# 6_Charger.net
KiCad netlist of a schematic drawn in Altium Designer
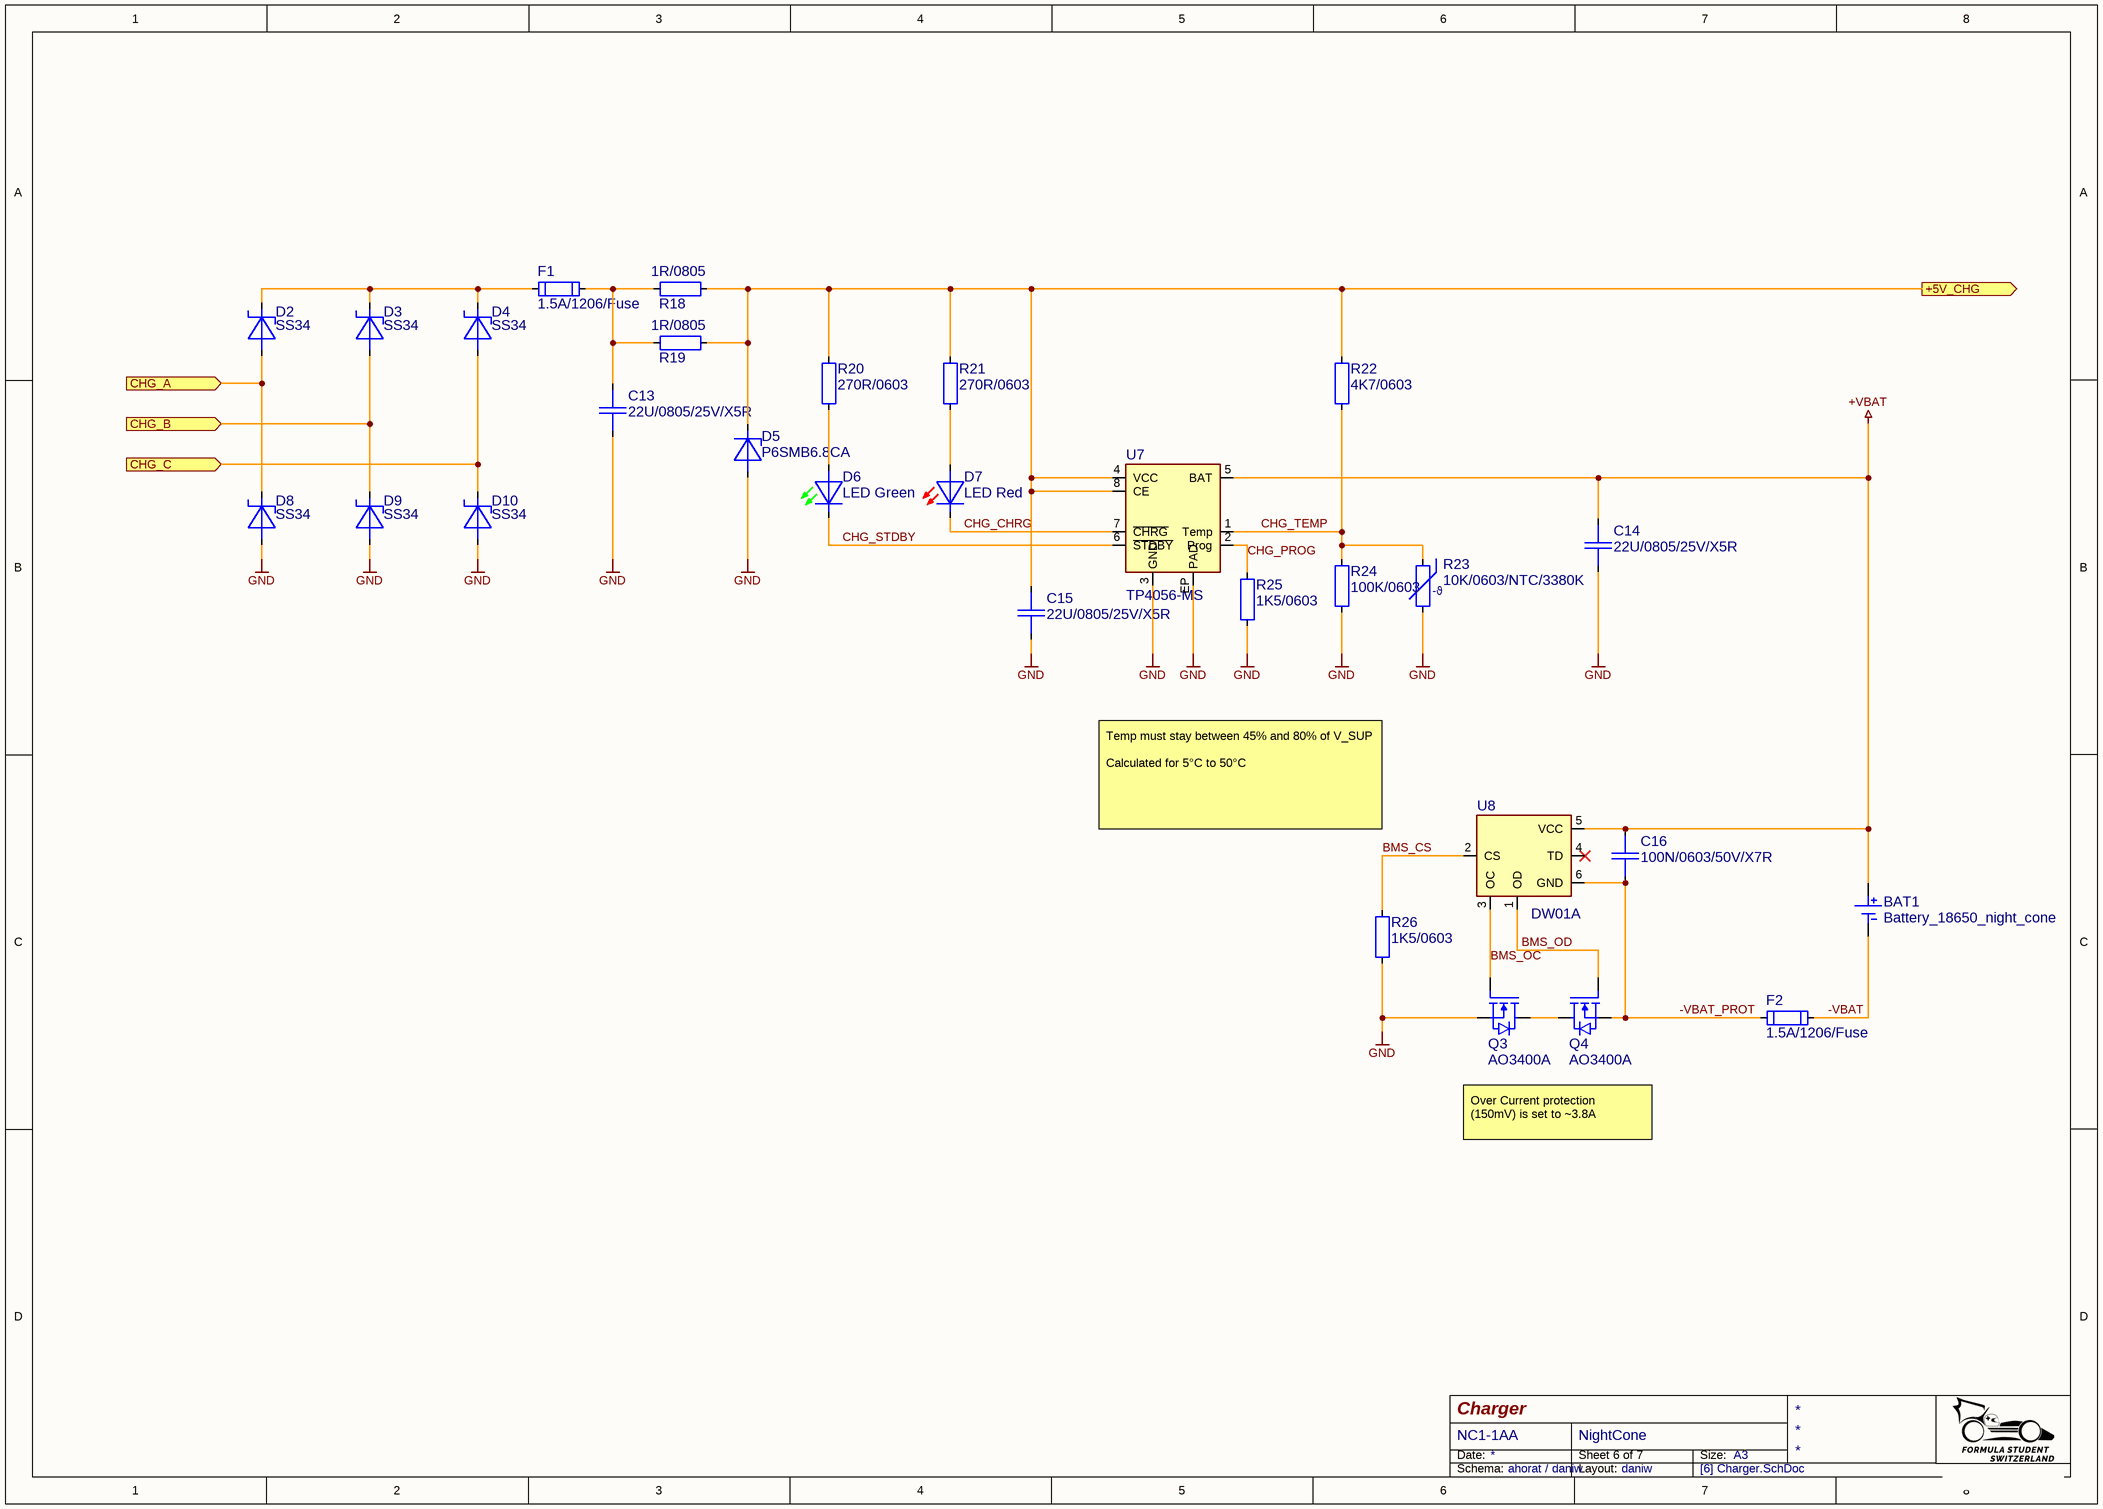
[diagram p0: [6] Charger.SchDoc]

(export (version "E")
  (design (tool "Eeschema 10.0.6"))
  (components
    (comp (ref "BAT1")
      (value "Battery_18650_night_cone")
      (footprint "Battery_18650_night_cone")
      (description "18650 Footprint with Hole for 18650 Battery")
      (fields (field (name "MANUFACTURER") "NONE"))
      (libsource (lib "daniw_altium_lib") (part "Battery_1"))
    )
    (comp (ref "C13")
      (value "22U/0805/25V/X5R")
      (footprint "CAP0805_X7R")
      (description "CAP SM 0805 22uF 25V X5R")
      (fields (field (name "MANUFACTURER") "GENERIC"))
      (libsource (lib "daniw_altium_lib") (part "C"))
    )
    (comp (ref "C14")
      (value "22U/0805/25V/X5R")
      (footprint "CAP0805_X7R")
      (description "CAP SM 0805 22uF 25V X5R")
      (fields (field (name "MANUFACTURER") "GENERIC"))
      (libsource (lib "daniw_altium_lib") (part "C"))
    )
    (comp (ref "C15")
      (value "22U/0805/25V/X5R")
      (footprint "CAP0805_X7R")
      (description "CAP SM 0805 22uF 25V X5R")
      (fields (field (name "MANUFACTURER") "GENERIC"))
      (libsource (lib "daniw_altium_lib") (part "C"))
    )
    (comp (ref "C16")
      (value "100N/0603/50V/X7R")
      (footprint "CAP0603_X7R")
      (description "CAP SM 0603 100nF 50V X7R")
      (fields (field (name "MANUFACTURER") "GENERIC"))
      (libsource (lib "daniw_altium_lib") (part "C"))
    )
    (comp (ref "D2")
      (value "SS34")
      (footprint "DIOM5226X230")
      (description "Si Shottky Diode 3A DO-214AC")
      (fields (field (name "MANUFACTURER") "GENERIC"))
      (libsource (lib "daniw_altium_lib") (part "D_Schottky"))
    )
    (comp (ref "D3")
      (value "SS34")
      (footprint "DIOM5226X230")
      (description "Si Shottky Diode 3A DO-214AC")
      (fields (field (name "MANUFACTURER") "GENERIC"))
      (libsource (lib "daniw_altium_lib") (part "D_Schottky"))
    )
    (comp (ref "D4")
      (value "SS34")
      (footprint "DIOM5226X230")
      (description "Si Shottky Diode 3A DO-214AC")
      (fields (field (name "MANUFACTURER") "GENERIC"))
      (libsource (lib "daniw_altium_lib") (part "D_Schottky"))
    )
    (comp (ref "D5")
      (value "P6SMB6.8CA")
      (footprint "DIOM5436X265")
      (description "10.5V 6.45V 5.8V SMB(DO-214AA) TVS")
      (fields (field (name "MANUFACTURER") "Littelfuse Inc."))
      (libsource (lib "daniw_altium_lib") (part "D_Zener"))
    )
    (comp (ref "D6")
      (value "LED Green")
      (footprint "LED0805_GREEN")
      (description "Generic LED Green 0805")
      (fields (field (name "PART NUMBER") "LED Green 0805") (field (name "MANUFACTURER") "GENERIC"))
      (libsource (lib "daniw_altium_lib") (part "LED_GREEN"))
    )
    (comp (ref "D7")
      (value "LED Red")
      (footprint "LED0805_RED")
      (description "Generic LED Red 0805")
      (fields (field (name "PART NUMBER") "LED Red 0805") (field (name "MANUFACTURER") "GENERIC"))
      (libsource (lib "daniw_altium_lib") (part "LED_RED"))
    )
    (comp (ref "D8")
      (value "SS34")
      (footprint "DIOM5226X230")
      (description "Si Shottky Diode 3A DO-214AC")
      (fields (field (name "MANUFACTURER") "GENERIC"))
      (libsource (lib "daniw_altium_lib") (part "D_Schottky"))
    )
    (comp (ref "D9")
      (value "SS34")
      (footprint "DIOM5226X230")
      (description "Si Shottky Diode 3A DO-214AC")
      (fields (field (name "MANUFACTURER") "GENERIC"))
      (libsource (lib "daniw_altium_lib") (part "D_Schottky"))
    )
    (comp (ref "D10")
      (value "SS34")
      (footprint "DIOM5226X230")
      (description "Si Shottky Diode 3A DO-214AC")
      (fields (field (name "MANUFACTURER") "GENERIC"))
      (libsource (lib "daniw_altium_lib") (part "D_Schottky"))
    )
    (comp (ref "F1")
      (value "1.5A/1206/Fuse")
      (footprint "Fuse1206-0.55-WW")
      (description "Multifuse 1206 1.5A")
      (fields (field (name "MANUFACTURER") "GENERIC"))
      (libsource (lib "daniw_altium_lib") (part "Fuse"))
    )
    (comp (ref "F2")
      (value "1.5A/1206/Fuse")
      (footprint "Fuse1206-0.55-WW")
      (description "Multifuse 1206 1.5A")
      (fields (field (name "MANUFACTURER") "GENERIC"))
      (libsource (lib "daniw_altium_lib") (part "Fuse"))
    )
    (comp (ref "Q3")
      (value "AO3400A")
      (footprint "SOT2395P280X125-3-SE")
      (description "30V N-Channel MOSFET")
      (fields (field (name "MANUFACTURER") "Alpha & Omega Semiconductor"))
      (libsource (lib "daniw_altium_lib") (part "MOSFET N_SOT23"))
    )
    (comp (ref "Q4")
      (value "AO3400A")
      (footprint "SOT2395P280X125-3-SE")
      (description "30V N-Channel MOSFET")
      (fields (field (name "MANUFACTURER") "Alpha & Omega Semiconductor"))
      (libsource (lib "daniw_altium_lib") (part "MOSFET N_SOT23"))
    )
    (comp (ref "R18")
      (value "1R/0805")
      (footprint "R0805-0.50-WW")
      (description "RES SM 0805 1R")
      (fields (field (name "MANUFACTURER") "GENERIC"))
      (libsource (lib "daniw_altium_lib") (part "R"))
    )
    (comp (ref "R19")
      (value "1R/0805")
      (footprint "R0805-0.50-WW")
      (description "RES SM 0805 1R")
      (fields (field (name "MANUFACTURER") "GENERIC"))
      (libsource (lib "daniw_altium_lib") (part "R"))
    )
    (comp (ref "R20")
      (value "270R/0603")
      (footprint "R0603-0.40-WW")
      (description "RES SM 0603 270R")
      (fields (field (name "MANUFACTURER") "GENERIC"))
      (libsource (lib "daniw_altium_lib") (part "R"))
    )
    (comp (ref "R21")
      (value "270R/0603")
      (footprint "R0603-0.40-WW")
      (description "RES SM 0603 270R")
      (fields (field (name "MANUFACTURER") "GENERIC"))
      (libsource (lib "daniw_altium_lib") (part "R"))
    )
    (comp (ref "R22")
      (value "4K7/0603")
      (footprint "R0603-0.40-WW")
      (description "RES SM 0603 4K7")
      (fields (field (name "MANUFACTURER") "GENERIC"))
      (libsource (lib "daniw_altium_lib") (part "R"))
    )
    (comp (ref "R23")
      (value "10K/0603/NTC/3380K")
      (footprint "R0603-0.40-WW")
      (description "RES NTC SM 0603 10K")
      (fields (field (name "MANUFACTURER") "GENERIC"))
      (libsource (lib "daniw_altium_lib") (part "R_NTC"))
    )
    (comp (ref "R24")
      (value "100K/0603")
      (footprint "R0603-0.40-WW")
      (description "RES SM 0603 100K")
      (fields (field (name "MANUFACTURER") "GENERIC"))
      (libsource (lib "daniw_altium_lib") (part "R"))
    )
    (comp (ref "R25")
      (value "1K5/0603")
      (footprint "R0603-0.40-WW")
      (description "RES SM 0603 1K5")
      (fields (field (name "MANUFACTURER") "GENERIC"))
      (libsource (lib "daniw_altium_lib") (part "R"))
    )
    (comp (ref "R26")
      (value "1K5/0603")
      (footprint "R0603-0.40-WW")
      (description "RES SM 0603 1K5")
      (fields (field (name "MANUFACTURER") "GENERIC"))
      (libsource (lib "daniw_altium_lib") (part "R"))
    )
    (comp (ref "U7")
      (value "TP4056-MS")
      (footprint "SOP127P600X155-9-TH330x240-NW")
      (description "1A Standalone Linear Li-lon Battery Charger with Thermal Regulation in SOP-8")
      (fields (field (name "MANUFACTURER") "MSKSEMI"))
      (libsource (lib "daniw_altium_lib") (part "TP4056"))
    )
    (comp (ref "U8")
      (value "DW01A")
      (footprint "SOT2395P280X125-6-SW")
      (description "Single Cell Lithium-ion battery protection IC")
      (fields (field (name "MANUFACTURER") "PUOLOP"))
      (libsource (lib "daniw_altium_lib") (part "DW01A"))
    )
  )
  (nets
    (net (code "1") (name "+VBAT") (class "Default")
      (node (ref "BAT1") (pin "1") (pinfunction "+_1") (pintype "passive"))
      (node (ref "C14") (pin "1") (pinfunction "1_1") (pintype "passive"))
      (node (ref "C16") (pin "1") (pinfunction "1_1") (pintype "passive"))
      (node (ref "U7") (pin "5") (pinfunction "BAT_5") (pintype "passive"))
      (node (ref "U8") (pin "5") (pinfunction "VCC_5") (pintype "passive"))
    )
    (net (code "2") (name "/+5V_CHG") (class "Default")
      (node (ref "C15") (pin "1") (pinfunction "1_1") (pintype "passive"))
      (node (ref "D5") (pin "1") (pinfunction "1_1") (pintype "passive"))
      (node (ref "R18") (pin "2") (pinfunction "2_2") (pintype "passive"))
      (node (ref "R19") (pin "2") (pinfunction "2_2") (pintype "passive"))
      (node (ref "R20") (pin "1") (pinfunction "1_1") (pintype "passive"))
      (node (ref "R21") (pin "1") (pinfunction "1_1") (pintype "passive"))
      (node (ref "R22") (pin "1") (pinfunction "1_1") (pintype "passive"))
      (node (ref "U7") (pin "4") (pinfunction "VCC_4") (pintype "passive"))
      (node (ref "U7") (pin "8") (pinfunction "CE_8") (pintype "passive"))
    )
    (net (code "3") (name "/-VBAT") (class "Default")
      (node (ref "BAT1") (pin "2") (pinfunction "-_2") (pintype "passive"))
      (node (ref "F2") (pin "1") (pinfunction "1_1") (pintype "passive"))
    )
    (net (code "4") (name "/-VBAT_PROT") (class "Default")
      (node (ref "C16") (pin "2") (pinfunction "2_2") (pintype "passive"))
      (node (ref "F2") (pin "2") (pinfunction "2_2") (pintype "passive"))
      (node (ref "Q4") (pin "2") (pinfunction "SOURCE_2") (pintype "passive"))
      (node (ref "U8") (pin "6") (pinfunction "GND_6") (pintype "passive"))
    )
    (net (code "5") (name "/BMS_CS") (class "Default")
      (node (ref "R26") (pin "1") (pinfunction "1_1") (pintype "passive"))
      (node (ref "U8") (pin "2") (pinfunction "CS_2") (pintype "passive"))
    )
    (net (code "6") (name "/BMS_OC") (class "Default")
      (node (ref "Q3") (pin "1") (pinfunction "GATE_1") (pintype "passive"))
      (node (ref "U8") (pin "3") (pinfunction "OC_3") (pintype "passive"))
    )
    (net (code "7") (name "/BMS_OD") (class "Default")
      (node (ref "Q4") (pin "1") (pinfunction "GATE_1") (pintype "passive"))
      (node (ref "U8") (pin "1") (pinfunction "OD_1") (pintype "passive"))
    )
    (net (code "8") (name "/CHG_A") (class "Default")
      (node (ref "D2") (pin "2") (pinfunction "2_2") (pintype "passive"))
      (node (ref "D8") (pin "1") (pinfunction "1_1") (pintype "passive"))
    )
    (net (code "9") (name "/CHG_B") (class "Default")
      (node (ref "D3") (pin "2") (pinfunction "2_2") (pintype "passive"))
      (node (ref "D9") (pin "1") (pinfunction "1_1") (pintype "passive"))
    )
    (net (code "10") (name "/CHG_C") (class "Default")
      (node (ref "D10") (pin "1") (pinfunction "1_1") (pintype "passive"))
      (node (ref "D4") (pin "2") (pinfunction "2_2") (pintype "passive"))
    )
    (net (code "11") (name "/CHG_CHRG") (class "Default")
      (node (ref "D7") (pin "1") (pinfunction "1_1") (pintype "passive"))
      (node (ref "U7") (pin "7") (pinfunction "~{CHRG}_7") (pintype "passive"))
    )
    (net (code "12") (name "/CHG_PROG") (class "Default")
      (node (ref "R25") (pin "1") (pinfunction "1_1") (pintype "passive"))
      (node (ref "U7") (pin "2") (pinfunction "Prog_2") (pintype "passive"))
    )
    (net (code "13") (name "/CHG_STDBY") (class "Default")
      (node (ref "D6") (pin "1") (pinfunction "1_1") (pintype "passive"))
      (node (ref "U7") (pin "6") (pinfunction "~{STDBY}_6") (pintype "passive"))
    )
    (net (code "14") (name "/CHG_TEMP") (class "Default")
      (node (ref "R22") (pin "2") (pinfunction "2_2") (pintype "passive"))
      (node (ref "R23") (pin "1") (pinfunction "1_1") (pintype "passive"))
      (node (ref "R24") (pin "1") (pinfunction "1_1") (pintype "passive"))
      (node (ref "U7") (pin "1") (pinfunction "Temp_1") (pintype "passive"))
    )
    (net (code "15") (name "GND") (class "Default")
      (node (ref "C13") (pin "2") (pinfunction "2_2") (pintype "passive"))
      (node (ref "C14") (pin "2") (pinfunction "2_2") (pintype "passive"))
      (node (ref "C15") (pin "2") (pinfunction "2_2") (pintype "passive"))
      (node (ref "D10") (pin "2") (pinfunction "2_2") (pintype "passive"))
      (node (ref "D5") (pin "2") (pinfunction "2_2") (pintype "passive"))
      (node (ref "D8") (pin "2") (pinfunction "2_2") (pintype "passive"))
      (node (ref "D9") (pin "2") (pinfunction "2_2") (pintype "passive"))
      (node (ref "Q3") (pin "2") (pinfunction "SOURCE_2") (pintype "passive"))
      (node (ref "R23") (pin "2") (pinfunction "2_2") (pintype "passive"))
      (node (ref "R24") (pin "2") (pinfunction "2_2") (pintype "passive"))
      (node (ref "R25") (pin "2") (pinfunction "2_2") (pintype "passive"))
      (node (ref "R26") (pin "2") (pinfunction "2_2") (pintype "passive"))
      (node (ref "U7") (pin "3") (pinfunction "GND_3") (pintype "passive"))
      (node (ref "U7") (pin "EP") (pinfunction "PAD_EP") (pintype "passive"))
    )
    (net (code "16") (name "Net-(C13-Pad1)") (class "Default")
      (node (ref "C13") (pin "1") (pinfunction "1_1") (pintype "passive"))
      (node (ref "F1") (pin "2") (pinfunction "2_2") (pintype "passive"))
      (node (ref "R18") (pin "1") (pinfunction "1_1") (pintype "passive"))
      (node (ref "R19") (pin "1") (pinfunction "1_1") (pintype "passive"))
    )
    (net (code "17") (name "Net-(D2-Pad1)") (class "Default")
      (node (ref "D2") (pin "1") (pinfunction "1_1") (pintype "passive"))
      (node (ref "D3") (pin "1") (pinfunction "1_1") (pintype "passive"))
      (node (ref "D4") (pin "1") (pinfunction "1_1") (pintype "passive"))
      (node (ref "F1") (pin "1") (pinfunction "1_1") (pintype "passive"))
    )
    (net (code "18") (name "Net-(D6-Pad2)") (class "Default")
      (node (ref "D6") (pin "2") (pinfunction "2_2") (pintype "passive"))
      (node (ref "R20") (pin "2") (pinfunction "2_2") (pintype "passive"))
    )
    (net (code "19") (name "Net-(D7-Pad2)") (class "Default")
      (node (ref "D7") (pin "2") (pinfunction "2_2") (pintype "passive"))
      (node (ref "R21") (pin "2") (pinfunction "2_2") (pintype "passive"))
    )
    (net (code "20") (name "Net-(Q3-DRAIN)") (class "Default")
      (node (ref "Q3") (pin "3") (pinfunction "DRAIN_3") (pintype "passive"))
      (node (ref "Q4") (pin "3") (pinfunction "DRAIN_3") (pintype "passive"))
    )
    (net (code "21") (name "unconnected-(U8-TD-Pad4)") (class "Default")
      (node (ref "U8") (pin "4") (pinfunction "TD_4") (pintype "passive+no_connect"))
    )
  )
)
